# ir-24v.net
KiCad netlist of a schematic drawn in Altium Designer
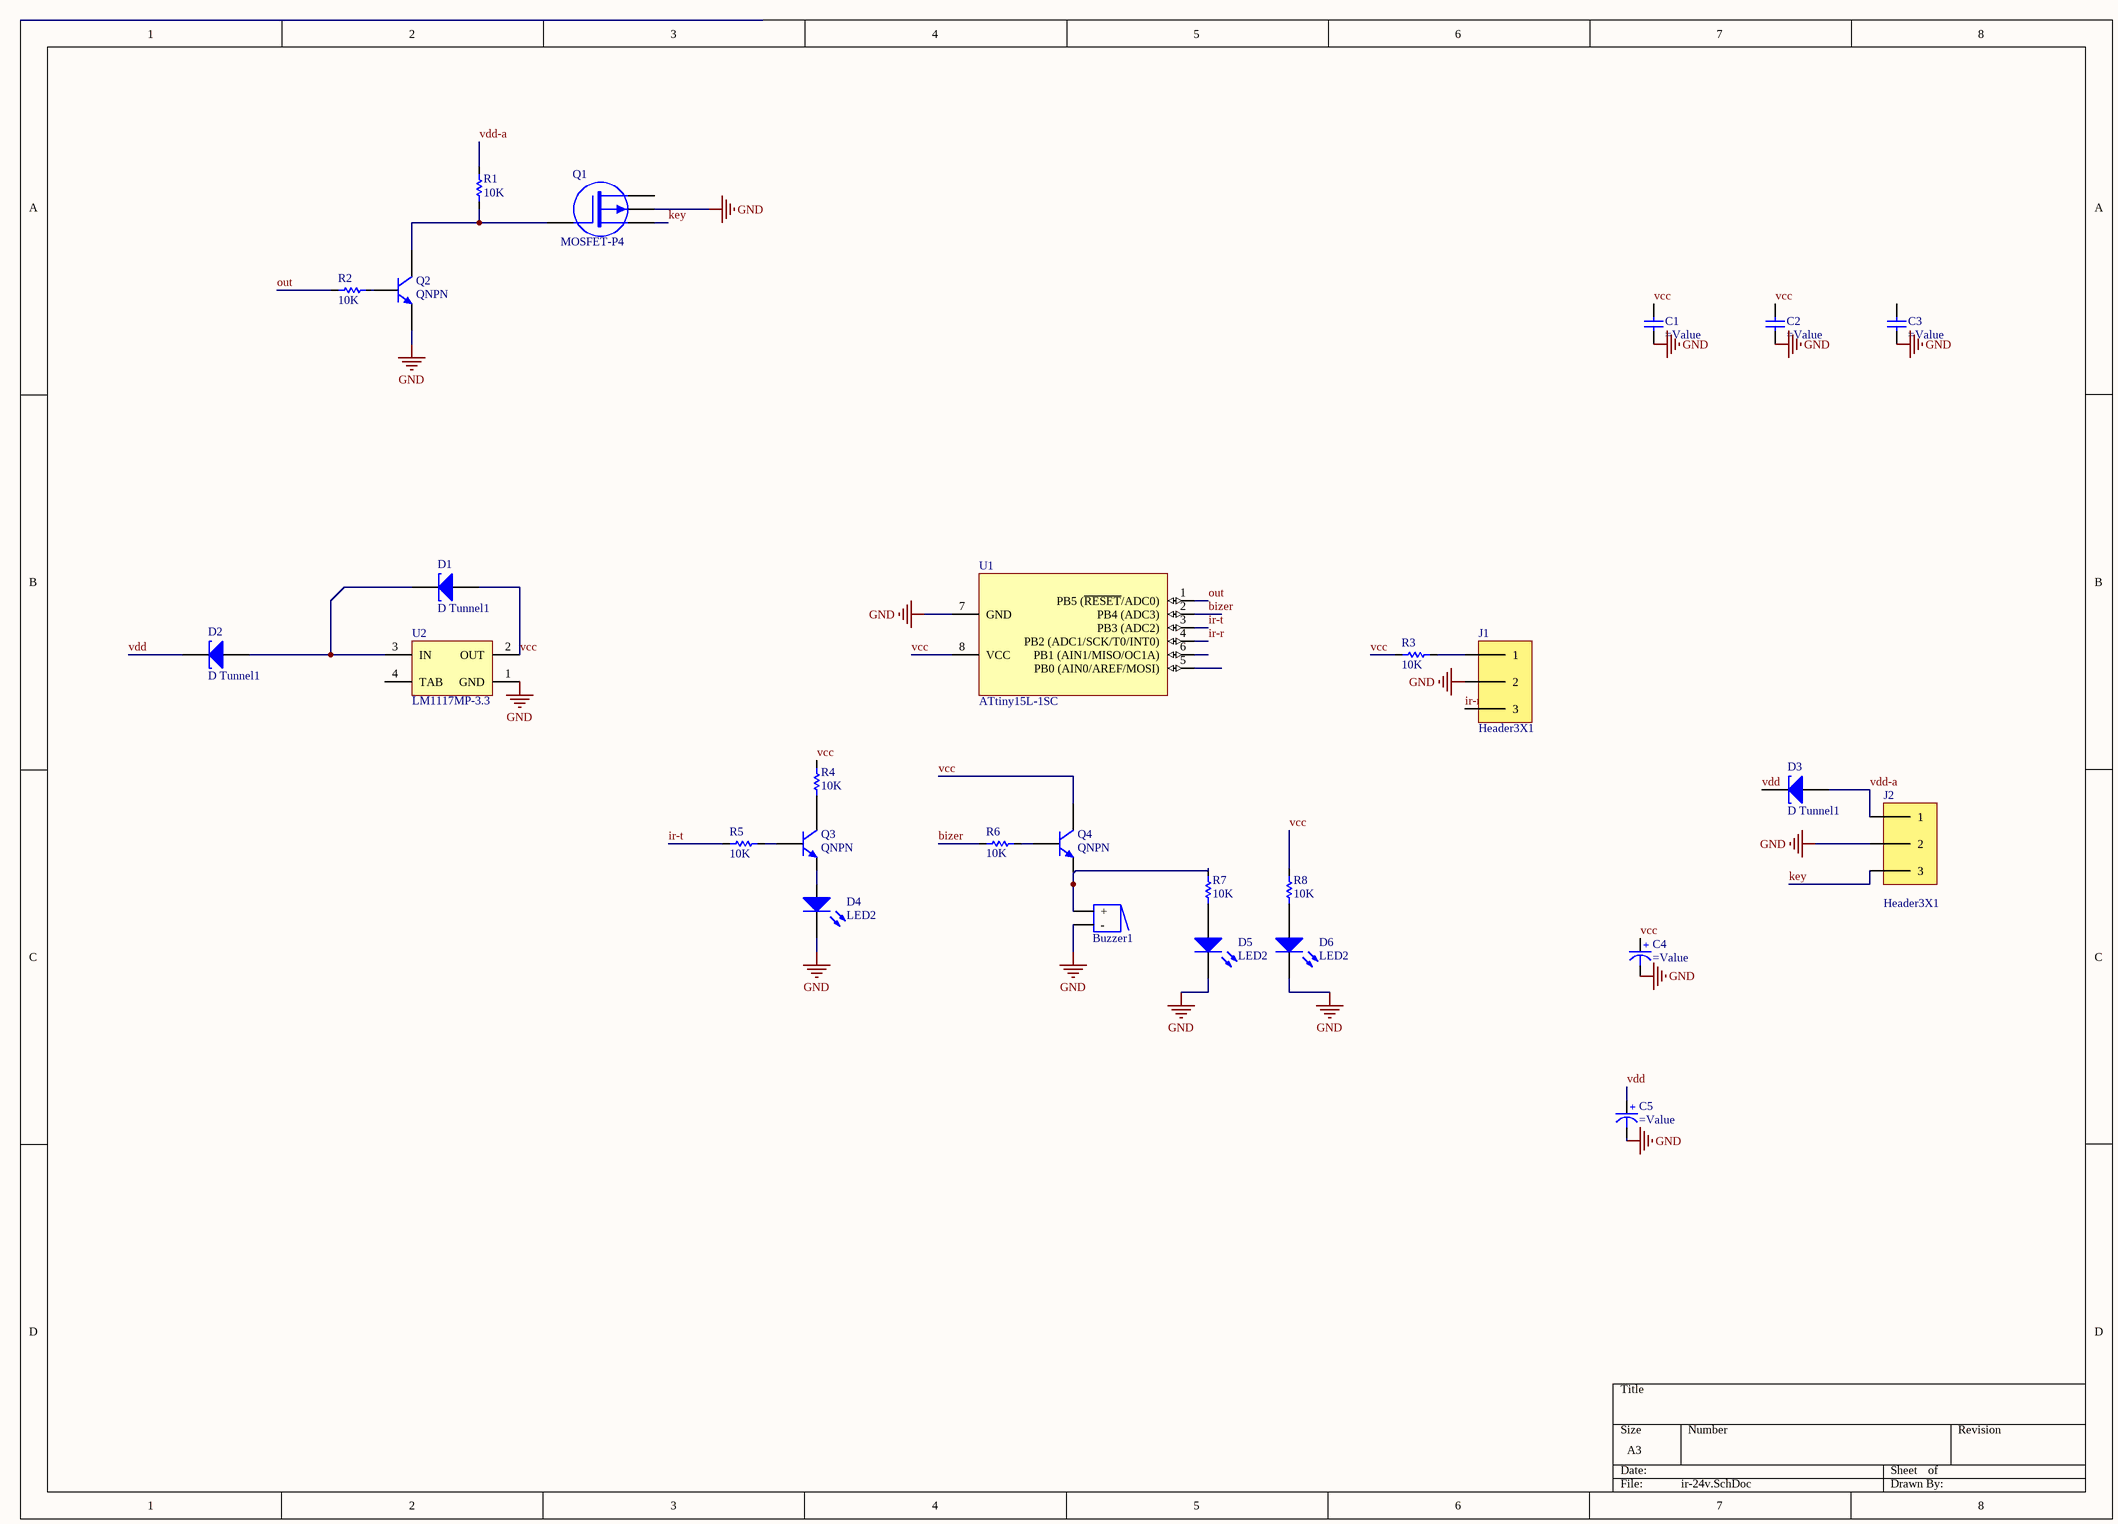
[diagram p0: ir-24v.SchDoc]

(export (version "E")
  (design (tool "Eeschema 10.0.6"))
  (components
    (comp (ref "Buzzer1")
      (value "Buzzer")
      (footprint "BUZZER")
      (fields (field (name "DESIGNER") "Seyed Mohsen Ghasemain"))
      (libsource (lib "PicPars.com_usefully_Library") (part "Buzzer"))
    )
    (comp (ref "C1")
      (value "~")
      (footprint "CAP 1206")
      (description "Capacitor")
      (libsource (lib "AltiumLib1") (part "Capacitor"))
    )
    (comp (ref "C2")
      (value "~")
      (footprint "CAP 1206")
      (description "Capacitor")
      (libsource (lib "AltiumLib1") (part "Capacitor"))
    )
    (comp (ref "C3")
      (value "~")
      (footprint "CAP 1206")
      (description "Capacitor")
      (libsource (lib "AltiumLib1") (part "Capacitor"))
    )
    (comp (ref "C4")
      (value "~")
      (footprint "ELEC-CAP-RAD10-20")
      (description "Electrolytic Capacitor")
      (libsource (lib "AltiumLib1") (part "Capacitor Electrolytic"))
    )
    (comp (ref "C5")
      (value "~")
      (footprint "ELEC-CAP-RAD15-30")
      (description "Electrolytic Capacitor")
      (libsource (lib "AltiumLib1") (part "Capacitor Electrolytic"))
    )
    (comp (ref "D1")
      (value "D Tunnel1")
      (footprint "3.2X1.6X1.1")
      (description "Tunnel Diode - RLC Model")
      (fields (field (name "PUBLISHER") "Altium Limited"))
      (libsource (lib "Miscellaneous Devices") (part "D Tunnel1"))
    )
    (comp (ref "D2")
      (value "D Tunnel1")
      (footprint "3.2X1.6X1.1")
      (description "Tunnel Diode - RLC Model")
      (fields (field (name "PUBLISHER") "Altium Limited"))
      (libsource (lib "Miscellaneous Devices") (part "D Tunnel1"))
    )
    (comp (ref "D3")
      (value "D Tunnel1")
      (footprint "3.2X1.6X1.1")
      (description "Tunnel Diode - RLC Model")
      (fields (field (name "PUBLISHER") "Altium Limited"))
      (libsource (lib "Miscellaneous Devices") (part "D Tunnel1"))
    )
    (comp (ref "D4")
      (value "LED2")
      (footprint "3.2X1.6X1.1")
      (description "Typical RED, GREEN, YELLOW, AMBER GaAs LED")
      (fields (field (name "PUBLISHER") "Altium Limited"))
      (libsource (lib "Miscellaneous Devices") (part "LED2"))
    )
    (comp (ref "D5")
      (value "LED2")
      (footprint "3.2X1.6X1.1")
      (description "Typical RED, GREEN, YELLOW, AMBER GaAs LED")
      (fields (field (name "PUBLISHER") "Altium Limited"))
      (libsource (lib "Miscellaneous Devices") (part "LED2"))
    )
    (comp (ref "D6")
      (value "LED2")
      (footprint "3.2X1.6X1.1")
      (description "Typical RED, GREEN, YELLOW, AMBER GaAs LED")
      (fields (field (name "PUBLISHER") "Altium Limited"))
      (libsource (lib "Miscellaneous Devices") (part "LED2"))
    )
    (comp (ref "J1")
      (value "Header3X1")
      (footprint "HEADER 3X1")
      (libsource (lib "AltiumLib1") (part "Header3X1"))
    )
    (comp (ref "J2")
      (value "Header3X1")
      (footprint "HEADER 3X1")
      (libsource (lib "AltiumLib1") (part "Header3X1"))
    )
    (comp (ref "Q1")
      (value "MOSFET-P4")
      (footprint "SOT223_N")
      (description "P-Channel MOSFET, Externally Terminated Substrate")
      (fields (field (name "PUBLISHER") "Altium Limited"))
      (libsource (lib "Miscellaneous Devices") (part "MOSFET-P4"))
    )
    (comp (ref "Q2")
      (value "QNPN")
      (footprint "SOT-23B_L")
      (description "NPN Bipolar Transistor")
      (fields (field (name "PUBLISHER") "Altium Limited"))
      (libsource (lib "Miscellaneous Devices") (part "QNPN"))
    )
    (comp (ref "Q3")
      (value "QNPN")
      (footprint "SOT-23B_L")
      (description "NPN Bipolar Transistor")
      (fields (field (name "PUBLISHER") "Altium Limited"))
      (libsource (lib "Miscellaneous Devices") (part "QNPN"))
    )
    (comp (ref "Q4")
      (value "QNPN")
      (footprint "SOT-23B_L")
      (description "NPN Bipolar Transistor")
      (fields (field (name "PUBLISHER") "Altium Limited"))
      (libsource (lib "Miscellaneous Devices") (part "QNPN"))
    )
    (comp (ref "R1")
      (value "10K")
      (footprint "RES 1206 (3216X08L)")
      (description "Resistor")
      (fields (field (name "TOLERANCE") "5%") (field (name "POWER") "1/4 W"))
      (libsource (lib "AltiumLib1") (part "Resistor"))
    )
    (comp (ref "R2")
      (value "10K")
      (footprint "RES 1206 (3216X08L)")
      (description "Resistor")
      (fields (field (name "TOLERANCE") "5%") (field (name "POWER") "1/4 W"))
      (libsource (lib "AltiumLib1") (part "Resistor"))
    )
    (comp (ref "R3")
      (value "10K")
      (footprint "RES 1206 (3216X08L)")
      (description "Resistor")
      (fields (field (name "TOLERANCE") "5%") (field (name "POWER") "1/4 W"))
      (libsource (lib "AltiumLib1") (part "Resistor"))
    )
    (comp (ref "R4")
      (value "10K")
      (footprint "RES 1206 (3216X08L)")
      (description "Resistor")
      (fields (field (name "TOLERANCE") "5%") (field (name "POWER") "1/4 W"))
      (libsource (lib "AltiumLib1") (part "Resistor"))
    )
    (comp (ref "R5")
      (value "10K")
      (footprint "RES 1206 (3216X08L)")
      (description "Resistor")
      (fields (field (name "TOLERANCE") "5%") (field (name "POWER") "1/4 W"))
      (libsource (lib "AltiumLib1") (part "Resistor"))
    )
    (comp (ref "R6")
      (value "10K")
      (footprint "RES 1206 (3216X08L)")
      (description "Resistor")
      (fields (field (name "TOLERANCE") "5%") (field (name "POWER") "1/4 W"))
      (libsource (lib "AltiumLib1") (part "Resistor"))
    )
    (comp (ref "R7")
      (value "10K")
      (footprint "RES 1206 (3216X08L)")
      (description "Resistor")
      (fields (field (name "TOLERANCE") "5%") (field (name "POWER") "1/4 W"))
      (libsource (lib "AltiumLib1") (part "Resistor"))
    )
    (comp (ref "R8")
      (value "10K")
      (footprint "RES 1206 (3216X08L)")
      (description "Resistor")
      (fields (field (name "TOLERANCE") "5%") (field (name "POWER") "1/4 W"))
      (libsource (lib "AltiumLib1") (part "Resistor"))
    )
    (comp (ref "U1")
      (value "ATtiny15L-1SC")
      (footprint "8S2_N")
      (description "8-Bit AVR Microcontroller with 1K Byte of Flash Memory")
      (fields (field (name "PUBLISHER") "Altium Limited"))
      (libsource (lib "Atmel Microcontroller 8-Bit AVR") (part "ATtiny15L-1SC"))
    )
    (comp (ref "U2")
      (value "LM1117MP-3.3")
      (footprint "Miscellaneous Devices:SOT89L")
      (description "800mA Low-Dropout Linear Regulator")
      (fields
        (field (name "MANUFACTURER") "National Semiconductor")
        (field (name "DIGIKEYPARTNUMBER") "LM1117MP-3.3CT-ND")
        (field (name "PUBLISHER") "Altium Limited")
      )
      (libsource (lib "NSC LDO") (part "LM1117MP-3.3"))
    )
  )
  (nets
    (net (code "1") (name "/bizer") (class "Default")
      (node (ref "R6") (pin "1") (pinfunction "1_1") (pintype "passive"))
      (node (ref "U1") (pin "2") (pinfunction "PB4_(ADC3)_2") (pintype "bidirectional"))
    )
    (net (code "2") (name "/ir-r") (class "Default")
      (node (ref "J1") (pin "3") (pinfunction "3_3") (pintype "passive"))
      (node (ref "U1") (pin "4") (pinfunction "PB2_(ADC1/SCK/T0/INT0)_4") (pintype "bidirectional"))
    )
    (net (code "3") (name "/ir-t") (class "Default")
      (node (ref "R5") (pin "1") (pinfunction "1_1") (pintype "passive"))
      (node (ref "U1") (pin "3") (pinfunction "PB3_(ADC2)_3") (pintype "bidirectional"))
    )
    (net (code "4") (name "/key") (class "Default")
      (node (ref "J2") (pin "3") (pinfunction "3_3") (pintype "passive"))
      (node (ref "Q1") (pin "4") (pinfunction "S_4") (pintype "passive"))
    )
    (net (code "5") (name "/out") (class "Default")
      (node (ref "R2") (pin "1") (pinfunction "1_1") (pintype "passive"))
      (node (ref "U1") (pin "1") (pinfunction "PB5_(~{RESET}/ADC0)_1") (pintype "bidirectional"))
    )
    (net (code "6") (name "/vcc") (class "Default")
      (node (ref "C1") (pin "2") (pinfunction "-_2") (pintype "passive"))
      (node (ref "C2") (pin "2") (pinfunction "-_2") (pintype "passive"))
      (node (ref "C4") (pin "2") (pinfunction "+_2") (pintype "passive"))
      (node (ref "D1") (pin "1") (pinfunction "A_1") (pintype "passive"))
      (node (ref "Q4") (pin "1") (pinfunction "C_1") (pintype "passive"))
      (node (ref "R3") (pin "2") (pinfunction "2_2") (pintype "passive"))
      (node (ref "R4") (pin "2") (pinfunction "2_2") (pintype "passive"))
      (node (ref "R8") (pin "2") (pinfunction "2_2") (pintype "passive"))
      (node (ref "U1") (pin "8") (pinfunction "VCC_8") (pintype "power_in"))
      (node (ref "U2") (pin "2") (pinfunction "OUT_2") (pintype "power_in"))
    )
    (net (code "7") (name "/vdd") (class "Default")
      (node (ref "C5") (pin "2") (pinfunction "+_2") (pintype "passive"))
      (node (ref "D2") (pin "2") (pinfunction "K_2") (pintype "passive"))
      (node (ref "D3") (pin "2") (pinfunction "K_2") (pintype "passive"))
    )
    (net (code "8") (name "/vdd-a") (class "Default")
      (node (ref "D3") (pin "1") (pinfunction "A_1") (pintype "passive"))
      (node (ref "J2") (pin "1") (pinfunction "1_1") (pintype "passive"))
      (node (ref "R1") (pin "2") (pinfunction "2_2") (pintype "passive"))
    )
    (net (code "9") (name "GND") (class "Default")
      (node (ref "Buzzer1") (pin "2") (pinfunction "-_2") (pintype "passive"))
      (node (ref "C1") (pin "1") (pinfunction "+_1") (pintype "passive"))
      (node (ref "C2") (pin "1") (pinfunction "+_1") (pintype "passive"))
      (node (ref "C3") (pin "1") (pinfunction "+_1") (pintype "passive"))
      (node (ref "C4") (pin "1") (pinfunction "-_1") (pintype "passive"))
      (node (ref "C5") (pin "1") (pinfunction "-_1") (pintype "passive"))
      (node (ref "D4") (pin "2") (pinfunction "K_2") (pintype "passive"))
      (node (ref "D5") (pin "2") (pinfunction "K_2") (pintype "passive"))
      (node (ref "D6") (pin "2") (pinfunction "K_2") (pintype "passive"))
      (node (ref "J1") (pin "2") (pinfunction "2_2") (pintype "passive"))
      (node (ref "J2") (pin "2") (pinfunction "2_2") (pintype "passive"))
      (node (ref "Q1") (pin "3") (pinfunction "U_3") (pintype "passive"))
      (node (ref "Q2") (pin "3") (pinfunction "E_3") (pintype "passive"))
      (node (ref "U1") (pin "7") (pinfunction "GND_7") (pintype "power_in"))
      (node (ref "U2") (pin "1") (pinfunction "GND_1") (pintype "power_in"))
    )
    (net (code "10") (name "Net-(Buzzer1-+)") (class "Default")
      (node (ref "Buzzer1") (pin "1") (pinfunction "+_1") (pintype "passive"))
      (node (ref "Q4") (pin "3") (pinfunction "E_3") (pintype "passive"))
      (node (ref "R7") (pin "2") (pinfunction "2_2") (pintype "passive"))
    )
    (net (code "11") (name "Net-(D1-K)") (class "Default")
      (node (ref "D1") (pin "2") (pinfunction "K_2") (pintype "passive"))
      (node (ref "D2") (pin "1") (pinfunction "A_1") (pintype "passive"))
      (node (ref "U2") (pin "3") (pinfunction "IN_3") (pintype "power_in"))
    )
    (net (code "12") (name "Net-(D4-A)") (class "Default")
      (node (ref "D4") (pin "1") (pinfunction "A_1") (pintype "passive"))
      (node (ref "Q3") (pin "3") (pinfunction "E_3") (pintype "passive"))
    )
    (net (code "13") (name "Net-(D5-A)") (class "Default")
      (node (ref "D5") (pin "1") (pinfunction "A_1") (pintype "passive"))
      (node (ref "R7") (pin "1") (pinfunction "1_1") (pintype "passive"))
    )
    (net (code "14") (name "Net-(D6-A)") (class "Default")
      (node (ref "D6") (pin "1") (pinfunction "A_1") (pintype "passive"))
      (node (ref "R8") (pin "1") (pinfunction "1_1") (pintype "passive"))
    )
    (net (code "15") (name "Net-(J1-Pad1)") (class "Default")
      (node (ref "J1") (pin "1") (pinfunction "1_1") (pintype "passive"))
      (node (ref "R3") (pin "1") (pinfunction "1_1") (pintype "passive"))
    )
    (net (code "16") (name "Net-(Q1-G)") (class "Default")
      (node (ref "Q1") (pin "1") (pinfunction "G_1") (pintype "passive"))
      (node (ref "Q2") (pin "1") (pinfunction "C_1") (pintype "passive"))
      (node (ref "R1") (pin "1") (pinfunction "1_1") (pintype "passive"))
    )
    (net (code "17") (name "Net-(Q2-B)") (class "Default")
      (node (ref "Q2") (pin "2") (pinfunction "B_2") (pintype "passive"))
      (node (ref "R2") (pin "2") (pinfunction "2_2") (pintype "passive"))
    )
    (net (code "18") (name "Net-(Q3-B)") (class "Default")
      (node (ref "Q3") (pin "2") (pinfunction "B_2") (pintype "passive"))
      (node (ref "R5") (pin "2") (pinfunction "2_2") (pintype "passive"))
    )
    (net (code "19") (name "Net-(Q3-C)") (class "Default")
      (node (ref "Q3") (pin "1") (pinfunction "C_1") (pintype "passive"))
      (node (ref "R4") (pin "1") (pinfunction "1_1") (pintype "passive"))
    )
    (net (code "20") (name "Net-(Q4-B)") (class "Default")
      (node (ref "Q4") (pin "2") (pinfunction "B_2") (pintype "passive"))
      (node (ref "R6") (pin "2") (pinfunction "2_2") (pintype "passive"))
    )
    (net (code "21") (name "unconnected-(C3---Pad2)") (class "Default")
      (node (ref "C3") (pin "2") (pinfunction "-_2") (pintype "passive"))
    )
    (net (code "22") (name "unconnected-(Q1-D-Pad2)") (class "Default")
      (node (ref "Q1") (pin "2") (pinfunction "D_2") (pintype "passive"))
    )
    (net (code "23") (name "unconnected-(U1-PB0_(AIN0{slash}AREF{slash}MOSI)-Pad5)") (class "Default")
      (node (ref "U1") (pin "5") (pinfunction "PB0_(AIN0/AREF/MOSI)_5") (pintype "bidirectional"))
    )
    (net (code "24") (name "unconnected-(U1-PB1_(AIN1{slash}MISO{slash}OC1A)-Pad6)") (class "Default")
      (node (ref "U1") (pin "6") (pinfunction "PB1_(AIN1/MISO/OC1A)_6") (pintype "bidirectional"))
    )
    (net (code "25") (name "unconnected-(U2-TAB-Pad4)") (class "Default")
      (node (ref "U2") (pin "4") (pinfunction "TAB_4") (pintype "power_in"))
    )
  )
)
